# Sheet1.net
KiCad netlist of a schematic drawn in Altium Designer
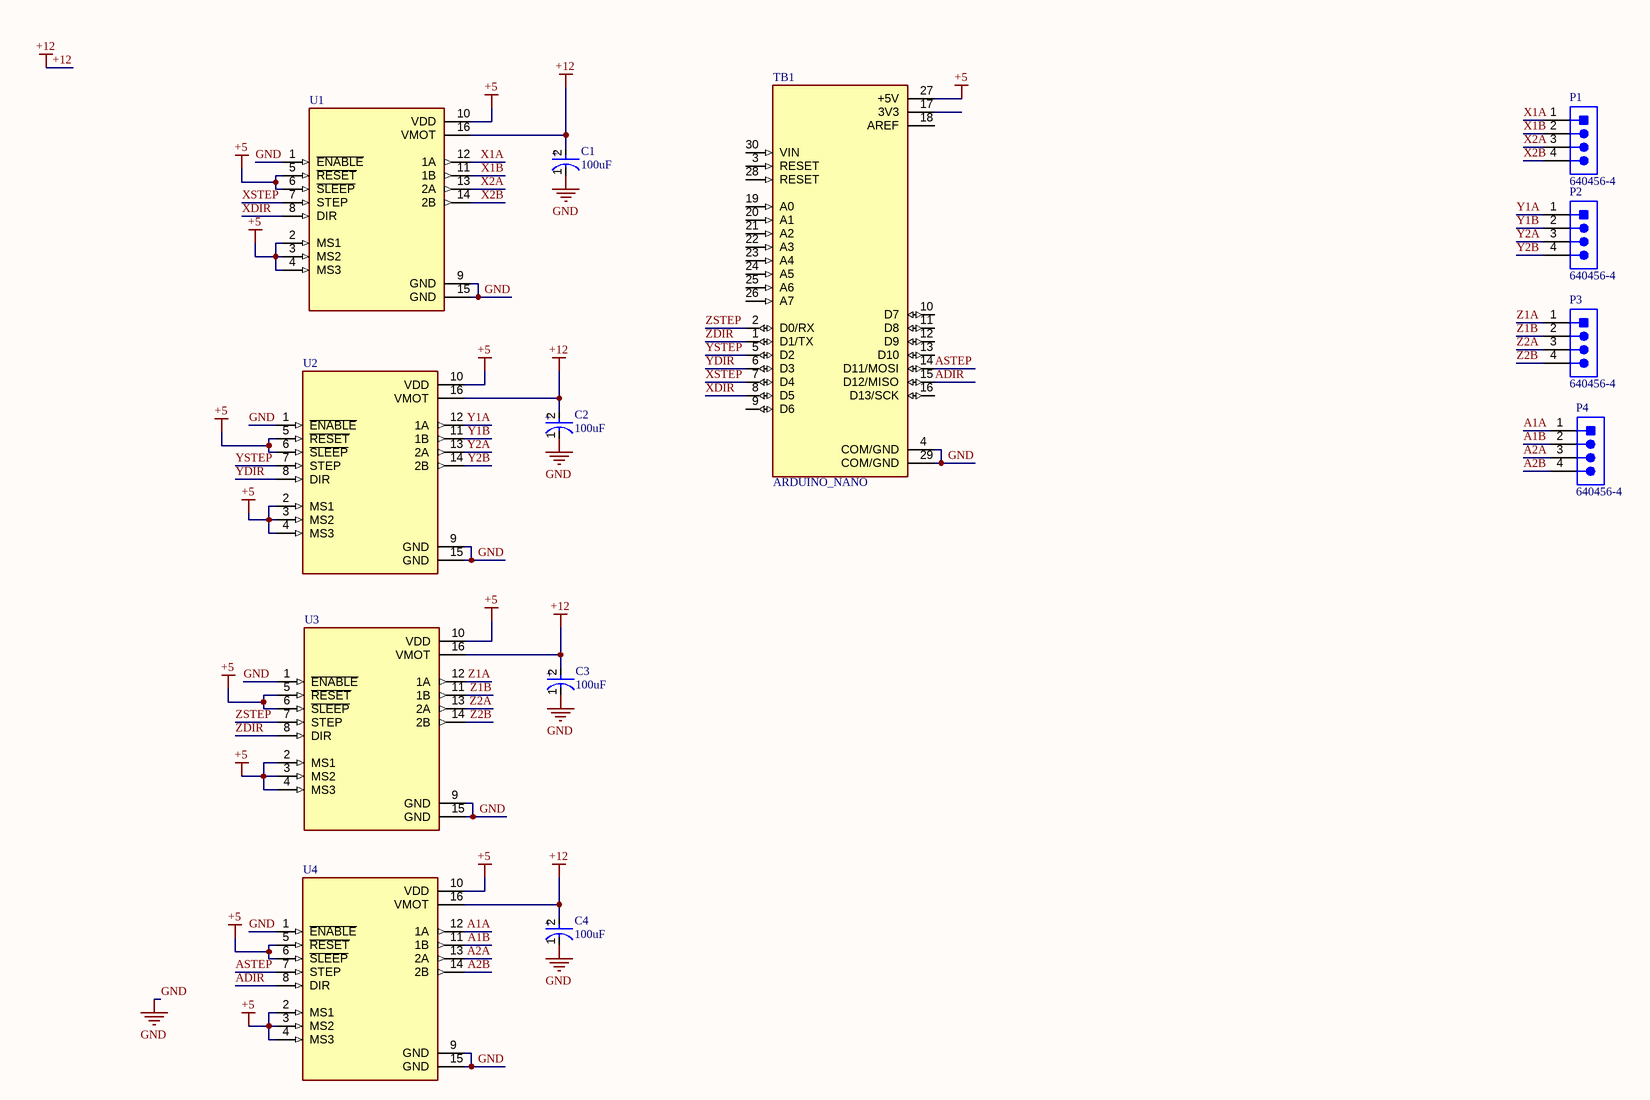
[diagram p0: Sheet1.SchDoc]

(export (version "E")
  (design (tool "Eeschema 10.0.6"))
  (components
    (comp (ref "C1")
      (value "100uF")
      (footprint "FP-RAD-TH-D_18_0_5-L_40_2-MFG")
      (description "Aluminum Electrolytic Capacitors (Radial Lead Type) 100uF ±20% 400V")
      (fields (field (name "VOLTAGE") "400V") (field (name "TOLERANCE") "20%"))
      (libsource (lib "Altium Content Vault") (part "a00bbbee19879c290e62620ae7e47b1"))
    )
    (comp (ref "C2")
      (value "100uF")
      (footprint "FP-RAD-TH-D_18_0_5-L_40_2-MFG")
      (description "Aluminum Electrolytic Capacitors (Radial Lead Type) 100uF ±20% 400V")
      (fields (field (name "VOLTAGE") "400V") (field (name "TOLERANCE") "20%"))
      (libsource (lib "Altium Content Vault") (part "a00bbbee19879c290e62620ae7e47b1"))
    )
    (comp (ref "C3")
      (value "100uF")
      (footprint "FP-RAD-TH-D_18_0_5-L_40_2-MFG")
      (description "Aluminum Electrolytic Capacitors (Radial Lead Type) 100uF ±20% 400V")
      (fields (field (name "VOLTAGE") "400V") (field (name "TOLERANCE") "20%"))
      (libsource (lib "Altium Content Vault") (part "a00bbbee19879c290e62620ae7e47b1"))
    )
    (comp (ref "C4")
      (value "100uF")
      (footprint "FP-RAD-TH-D_18_0_5-L_40_2-MFG")
      (fields (field (name "VOLTAGE") "400V") (field (name "TOLERANCE") "20%"))
      (libsource (lib "Altium Content Vault") (part "a00bbbee19879c290e62620ae7e47b1"))
    )
    (comp (ref "P1")
      (value "640456-4")
      (footprint "TECO-640456-4")
      (description "Male Header, Pitch 2.54 mm, 1 x 4 Position, Height 10.03 mm, Tail Length 3.56 mm, RoHS, Bulk")
      (fields (field (name "MANUFACTURER") "TE Connectivity"))
      (libsource (lib "Altium Content Vault") (part "CN-1P-M-R4"))
    )
    (comp (ref "P2")
      (value "640456-4")
      (footprint "TECO-640456-4")
      (description "Male Header, Pitch 2.54 mm, 1 x 4 Position, Height 10.03 mm, Tail Length 3.56 mm, RoHS, Bulk")
      (fields (field (name "MANUFACTURER") "TE Connectivity"))
      (libsource (lib "Altium Content Vault") (part "CN-1P-M-R4"))
    )
    (comp (ref "P3")
      (value "640456-4")
      (footprint "TECO-640456-4")
      (description "Male Header, Pitch 2.54 mm, 1 x 4 Position, Height 10.03 mm, Tail Length 3.56 mm, RoHS, Bulk")
      (fields (field (name "MANUFACTURER") "TE Connectivity"))
      (libsource (lib "Altium Content Vault") (part "CN-1P-M-R4"))
    )
    (comp (ref "P4")
      (value "640456-4")
      (footprint "TECO-640456-4")
      (description "Male Header, Pitch 2.54 mm, 1 x 4 Position, Height 10.03 mm, Tail Length 3.56 mm, RoHS, Bulk")
      (fields (field (name "MANUFACTURER") "TE Connectivity"))
      (libsource (lib "Altium Content Vault") (part "CN-1P-M-R4"))
    )
    (comp (ref "TB1")
      (value "ARDUINO_NANO")
      (footprint "SHIELD_ARDUINO_NANO")
      (description "Small, complete, and breadboard-friendly board based on the ATmega328 (Arduino Nano 3.x)")
      (fields (field (name "MP") "Arduino Nano") (field (name "MF") "Arduino"))
      (libsource (lib "ARDUINO_NANO") (part "ARDUINO_NANO"))
    )
    (comp (ref "U1")
      (value "A4988_STEPPER_MOTOR_DRIVER_CARRIER_BLACK")
      (footprint "MODULE_A4988_STEPPER_MOTOR_DRIVER_CARRIER_BLACK")
      (fields (field (name "MF") "Pololu") (field (name "MP") "A4988 STEPPER MOTOR DRIVER CARRIER BLACK"))
      (libsource (lib "A4988_STEPPER_MOTOR_DRIVER_CARRIER_BLACK") (part "A4988_STEPPER_MOTOR_DRIVER_CARRIER_BLACK"))
    )
    (comp (ref "U2")
      (value "4988_STEPPER_MOTOR_DRIVER_CARRIER_BLACK")
      (footprint "MODULE_A4988_STEPPER_MOTOR_DRIVER_CARRIER_BLACK")
      (fields (field (name "MF") "Pololu") (field (name "MP") "A4988 STEPPER MOTOR DRIVER CARRIER BLACK"))
      (libsource (lib "A4988_STEPPER_MOTOR_DRIVER_CARRIER_BLACK") (part "A4988_STEPPER_MOTOR_DRIVER_CARRIER_BLACK"))
    )
    (comp (ref "U3")
      (value "A4988_STEPPER_MOTOR_DRIVER_CARRIER_BLACK")
      (footprint "MODULE_A4988_STEPPER_MOTOR_DRIVER_CARRIER_BLACK")
      (fields (field (name "MF") "Pololu") (field (name "MP") "A4988 STEPPER MOTOR DRIVER CARRIER BLACK"))
      (libsource (lib "A4988_STEPPER_MOTOR_DRIVER_CARRIER_BLACK") (part "A4988_STEPPER_MOTOR_DRIVER_CARRIER_BLACK"))
    )
    (comp (ref "U4")
      (value "A4988_STEPPER_MOTOR_DRIVER_CARRIER_BLACK")
      (footprint "MODULE_A4988_STEPPER_MOTOR_DRIVER_CARRIER_BLACK")
      (fields (field (name "MF") "Pololu") (field (name "MP") "A4988 STEPPER MOTOR DRIVER CARRIER BLACK"))
      (libsource (lib "A4988_STEPPER_MOTOR_DRIVER_CARRIER_BLACK") (part "A4988_STEPPER_MOTOR_DRIVER_CARRIER_BLACK"))
    )
  )
  (nets
    (net (code "1") (name "+5") (class "Default")
      (node (ref "TB1") (pin "27") (pinfunction "+5V_27") (pintype "power_in"))
      (node (ref "U1") (pin "10") (pinfunction "VDD_10") (pintype "power_in"))
      (node (ref "U1") (pin "2") (pinfunction "MS1_2") (pintype "input"))
      (node (ref "U1") (pin "3") (pinfunction "MS2_3") (pintype "input"))
      (node (ref "U1") (pin "4") (pinfunction "MS3_4") (pintype "input"))
      (node (ref "U1") (pin "5") (pinfunction "~{RESET}_5") (pintype "input"))
      (node (ref "U1") (pin "6") (pinfunction "~{SLEEP}_6") (pintype "input"))
      (node (ref "U2") (pin "10") (pinfunction "VDD_10") (pintype "power_in"))
      (node (ref "U2") (pin "2") (pinfunction "MS1_2") (pintype "input"))
      (node (ref "U2") (pin "3") (pinfunction "MS2_3") (pintype "input"))
      (node (ref "U2") (pin "4") (pinfunction "MS3_4") (pintype "input"))
      (node (ref "U2") (pin "5") (pinfunction "~{RESET}_5") (pintype "input"))
      (node (ref "U2") (pin "6") (pinfunction "~{SLEEP}_6") (pintype "input"))
      (node (ref "U3") (pin "10") (pinfunction "VDD_10") (pintype "power_in"))
      (node (ref "U3") (pin "2") (pinfunction "MS1_2") (pintype "input"))
      (node (ref "U3") (pin "3") (pinfunction "MS2_3") (pintype "input"))
      (node (ref "U3") (pin "4") (pinfunction "MS3_4") (pintype "input"))
      (node (ref "U3") (pin "5") (pinfunction "~{RESET}_5") (pintype "input"))
      (node (ref "U3") (pin "6") (pinfunction "~{SLEEP}_6") (pintype "input"))
      (node (ref "U4") (pin "10") (pinfunction "VDD_10") (pintype "power_in"))
      (node (ref "U4") (pin "2") (pinfunction "MS1_2") (pintype "input"))
      (node (ref "U4") (pin "3") (pinfunction "MS2_3") (pintype "input"))
      (node (ref "U4") (pin "4") (pinfunction "MS3_4") (pintype "input"))
      (node (ref "U4") (pin "5") (pinfunction "~{RESET}_5") (pintype "input"))
      (node (ref "U4") (pin "6") (pinfunction "~{SLEEP}_6") (pintype "input"))
    )
    (net (code "2") (name "+12") (class "Default")
      (node (ref "C1") (pin "2") (pinfunction "A_2") (pintype "passive"))
      (node (ref "C2") (pin "2") (pinfunction "A_2") (pintype "passive"))
      (node (ref "C3") (pin "2") (pinfunction "A_2") (pintype "passive"))
      (node (ref "C4") (pin "2") (pinfunction "A_2") (pintype "passive"))
      (node (ref "U1") (pin "16") (pinfunction "VMOT_16") (pintype "power_in"))
      (node (ref "U2") (pin "16") (pinfunction "VMOT_16") (pintype "power_in"))
      (node (ref "U3") (pin "16") (pinfunction "VMOT_16") (pintype "power_in"))
      (node (ref "U4") (pin "16") (pinfunction "VMOT_16") (pintype "power_in"))
    )
    (net (code "3") (name "/A1A") (class "Default")
      (node (ref "P4") (pin "1") (pinfunction "1_1") (pintype "passive"))
      (node (ref "U4") (pin "12") (pinfunction "1A_12") (pintype "output"))
    )
    (net (code "4") (name "/A1B") (class "Default")
      (node (ref "P4") (pin "2") (pinfunction "2_2") (pintype "passive"))
      (node (ref "U4") (pin "11") (pinfunction "1B_11") (pintype "output"))
    )
    (net (code "5") (name "/A2A") (class "Default")
      (node (ref "P4") (pin "3") (pinfunction "3_3") (pintype "passive"))
      (node (ref "U4") (pin "13") (pinfunction "2A_13") (pintype "output"))
    )
    (net (code "6") (name "/A2B") (class "Default")
      (node (ref "P4") (pin "4") (pinfunction "4_4") (pintype "passive"))
      (node (ref "U4") (pin "14") (pinfunction "2B_14") (pintype "output"))
    )
    (net (code "7") (name "/ADIR") (class "Default")
      (node (ref "TB1") (pin "15") (pinfunction "D12/MISO_15") (pintype "bidirectional"))
      (node (ref "U4") (pin "8") (pinfunction "DIR_8") (pintype "input"))
    )
    (net (code "8") (name "/ASTEP") (class "Default")
      (node (ref "TB1") (pin "14") (pinfunction "D11/MOSI_14") (pintype "bidirectional"))
      (node (ref "U4") (pin "7") (pinfunction "STEP_7") (pintype "input"))
    )
    (net (code "9") (name "/X1A") (class "Default")
      (node (ref "P1") (pin "1") (pinfunction "1_1") (pintype "passive"))
      (node (ref "U1") (pin "12") (pinfunction "1A_12") (pintype "output"))
    )
    (net (code "10") (name "/X1B") (class "Default")
      (node (ref "P1") (pin "2") (pinfunction "2_2") (pintype "passive"))
      (node (ref "U1") (pin "11") (pinfunction "1B_11") (pintype "output"))
    )
    (net (code "11") (name "/X2A") (class "Default")
      (node (ref "P1") (pin "3") (pinfunction "3_3") (pintype "passive"))
      (node (ref "U1") (pin "13") (pinfunction "2A_13") (pintype "output"))
    )
    (net (code "12") (name "/X2B") (class "Default")
      (node (ref "P1") (pin "4") (pinfunction "4_4") (pintype "passive"))
      (node (ref "U1") (pin "14") (pinfunction "2B_14") (pintype "output"))
    )
    (net (code "13") (name "/XDIR") (class "Default")
      (node (ref "TB1") (pin "8") (pinfunction "D5_8") (pintype "bidirectional"))
      (node (ref "U1") (pin "8") (pinfunction "DIR_8") (pintype "input"))
    )
    (net (code "14") (name "/XSTEP") (class "Default")
      (node (ref "TB1") (pin "7") (pinfunction "D4_7") (pintype "bidirectional"))
      (node (ref "U1") (pin "7") (pinfunction "STEP_7") (pintype "input"))
    )
    (net (code "15") (name "/Y1A") (class "Default")
      (node (ref "P2") (pin "1") (pinfunction "1_1") (pintype "passive"))
      (node (ref "U2") (pin "12") (pinfunction "1A_12") (pintype "output"))
    )
    (net (code "16") (name "/Y1B") (class "Default")
      (node (ref "P2") (pin "2") (pinfunction "2_2") (pintype "passive"))
      (node (ref "U2") (pin "11") (pinfunction "1B_11") (pintype "output"))
    )
    (net (code "17") (name "/Y2A") (class "Default")
      (node (ref "P2") (pin "3") (pinfunction "3_3") (pintype "passive"))
      (node (ref "U2") (pin "13") (pinfunction "2A_13") (pintype "output"))
    )
    (net (code "18") (name "/Y2B") (class "Default")
      (node (ref "P2") (pin "4") (pinfunction "4_4") (pintype "passive"))
      (node (ref "U2") (pin "14") (pinfunction "2B_14") (pintype "output"))
    )
    (net (code "19") (name "/YDIR") (class "Default")
      (node (ref "TB1") (pin "6") (pinfunction "D3_6") (pintype "bidirectional"))
      (node (ref "U2") (pin "8") (pinfunction "DIR_8") (pintype "input"))
    )
    (net (code "20") (name "/YSTEP") (class "Default")
      (node (ref "TB1") (pin "5") (pinfunction "D2_5") (pintype "bidirectional"))
      (node (ref "U2") (pin "7") (pinfunction "STEP_7") (pintype "input"))
    )
    (net (code "21") (name "/Z1A") (class "Default")
      (node (ref "P3") (pin "1") (pinfunction "1_1") (pintype "passive"))
      (node (ref "U3") (pin "12") (pinfunction "1A_12") (pintype "output"))
    )
    (net (code "22") (name "/Z1B") (class "Default")
      (node (ref "P3") (pin "2") (pinfunction "2_2") (pintype "passive"))
      (node (ref "U3") (pin "11") (pinfunction "1B_11") (pintype "output"))
    )
    (net (code "23") (name "/Z2A") (class "Default")
      (node (ref "P3") (pin "3") (pinfunction "3_3") (pintype "passive"))
      (node (ref "U3") (pin "13") (pinfunction "2A_13") (pintype "output"))
    )
    (net (code "24") (name "/Z2B") (class "Default")
      (node (ref "P3") (pin "4") (pinfunction "4_4") (pintype "passive"))
      (node (ref "U3") (pin "14") (pinfunction "2B_14") (pintype "output"))
    )
    (net (code "25") (name "/ZDIR") (class "Default")
      (node (ref "TB1") (pin "1") (pinfunction "D1/TX_1") (pintype "bidirectional"))
      (node (ref "U3") (pin "8") (pinfunction "DIR_8") (pintype "input"))
    )
    (net (code "26") (name "/ZSTEP") (class "Default")
      (node (ref "TB1") (pin "2") (pinfunction "D0/RX_2") (pintype "bidirectional"))
      (node (ref "U3") (pin "7") (pinfunction "STEP_7") (pintype "input"))
    )
    (net (code "27") (name "GND") (class "Default")
      (node (ref "C1") (pin "1") (pinfunction "C_1") (pintype "passive"))
      (node (ref "C2") (pin "1") (pinfunction "C_1") (pintype "passive"))
      (node (ref "C3") (pin "1") (pinfunction "C_1") (pintype "passive"))
      (node (ref "C4") (pin "1") (pinfunction "C_1") (pintype "passive"))
      (node (ref "TB1") (pin "29") (pinfunction "COM/GND_29") (pintype "power_in"))
      (node (ref "TB1") (pin "4") (pinfunction "COM/GND_4") (pintype "power_in"))
      (node (ref "U1") (pin "1") (pinfunction "~{ENABLE}_1") (pintype "input"))
      (node (ref "U1") (pin "15") (pinfunction "GND_15") (pintype "power_in"))
      (node (ref "U1") (pin "9") (pinfunction "GND_9") (pintype "power_in"))
      (node (ref "U2") (pin "1") (pinfunction "~{ENABLE}_1") (pintype "input"))
      (node (ref "U2") (pin "15") (pinfunction "GND_15") (pintype "power_in"))
      (node (ref "U2") (pin "9") (pinfunction "GND_9") (pintype "power_in"))
      (node (ref "U3") (pin "1") (pinfunction "~{ENABLE}_1") (pintype "input"))
      (node (ref "U3") (pin "15") (pinfunction "GND_15") (pintype "power_in"))
      (node (ref "U3") (pin "9") (pinfunction "GND_9") (pintype "power_in"))
      (node (ref "U4") (pin "1") (pinfunction "~{ENABLE}_1") (pintype "input"))
      (node (ref "U4") (pin "15") (pinfunction "GND_15") (pintype "power_in"))
      (node (ref "U4") (pin "9") (pinfunction "GND_9") (pintype "power_in"))
    )
    (net (code "28") (name "unconnected-(TB1-3V3-Pad17)") (class "Default")
      (node (ref "TB1") (pin "17") (pinfunction "3V3_17") (pintype "power_in"))
    )
    (net (code "29") (name "unconnected-(TB1-A0-Pad19)") (class "Default")
      (node (ref "TB1") (pin "19") (pinfunction "A0_19") (pintype "input"))
    )
    (net (code "30") (name "unconnected-(TB1-A1-Pad20)") (class "Default")
      (node (ref "TB1") (pin "20") (pinfunction "A1_20") (pintype "input"))
    )
    (net (code "31") (name "unconnected-(TB1-A2-Pad21)") (class "Default")
      (node (ref "TB1") (pin "21") (pinfunction "A2_21") (pintype "input"))
    )
    (net (code "32") (name "unconnected-(TB1-A3-Pad22)") (class "Default")
      (node (ref "TB1") (pin "22") (pinfunction "A3_22") (pintype "input"))
    )
    (net (code "33") (name "unconnected-(TB1-A4-Pad23)") (class "Default")
      (node (ref "TB1") (pin "23") (pinfunction "A4_23") (pintype "input"))
    )
    (net (code "34") (name "unconnected-(TB1-A5-Pad24)") (class "Default")
      (node (ref "TB1") (pin "24") (pinfunction "A5_24") (pintype "input"))
    )
    (net (code "35") (name "unconnected-(TB1-A6-Pad25)") (class "Default")
      (node (ref "TB1") (pin "25") (pinfunction "A6_25") (pintype "input"))
    )
    (net (code "36") (name "unconnected-(TB1-A7-Pad26)") (class "Default")
      (node (ref "TB1") (pin "26") (pinfunction "A7_26") (pintype "input"))
    )
    (net (code "37") (name "unconnected-(TB1-AREF-Pad18)") (class "Default")
      (node (ref "TB1") (pin "18") (pinfunction "AREF_18") (pintype "power_in"))
    )
    (net (code "38") (name "unconnected-(TB1-D6-Pad9)") (class "Default")
      (node (ref "TB1") (pin "9") (pinfunction "D6_9") (pintype "bidirectional"))
    )
    (net (code "39") (name "unconnected-(TB1-D7-Pad10)") (class "Default")
      (node (ref "TB1") (pin "10") (pinfunction "D7_10") (pintype "bidirectional"))
    )
    (net (code "40") (name "unconnected-(TB1-D8-Pad11)") (class "Default")
      (node (ref "TB1") (pin "11") (pinfunction "D8_11") (pintype "bidirectional"))
    )
    (net (code "41") (name "unconnected-(TB1-D9-Pad12)") (class "Default")
      (node (ref "TB1") (pin "12") (pinfunction "D9_12") (pintype "bidirectional"))
    )
    (net (code "42") (name "unconnected-(TB1-D10-Pad13)") (class "Default")
      (node (ref "TB1") (pin "13") (pinfunction "D10_13") (pintype "bidirectional"))
    )
    (net (code "43") (name "unconnected-(TB1-D13{slash}SCK-Pad16)") (class "Default")
      (node (ref "TB1") (pin "16") (pinfunction "D13/SCK_16") (pintype "bidirectional"))
    )
    (net (code "44") (name "unconnected-(TB1-RESET-Pad3)") (class "Default")
      (node (ref "TB1") (pin "3") (pinfunction "RESET_3") (pintype "input"))
    )
    (net (code "45") (name "unconnected-(TB1-RESET-Pad28)") (class "Default")
      (node (ref "TB1") (pin "28") (pinfunction "RESET_28") (pintype "input"))
    )
    (net (code "46") (name "unconnected-(TB1-VIN-Pad30)") (class "Default")
      (node (ref "TB1") (pin "30") (pinfunction "VIN_30") (pintype "input"))
    )
  )
)
